# develboard.net
KiCad netlist of a schematic drawn in Altium Designer
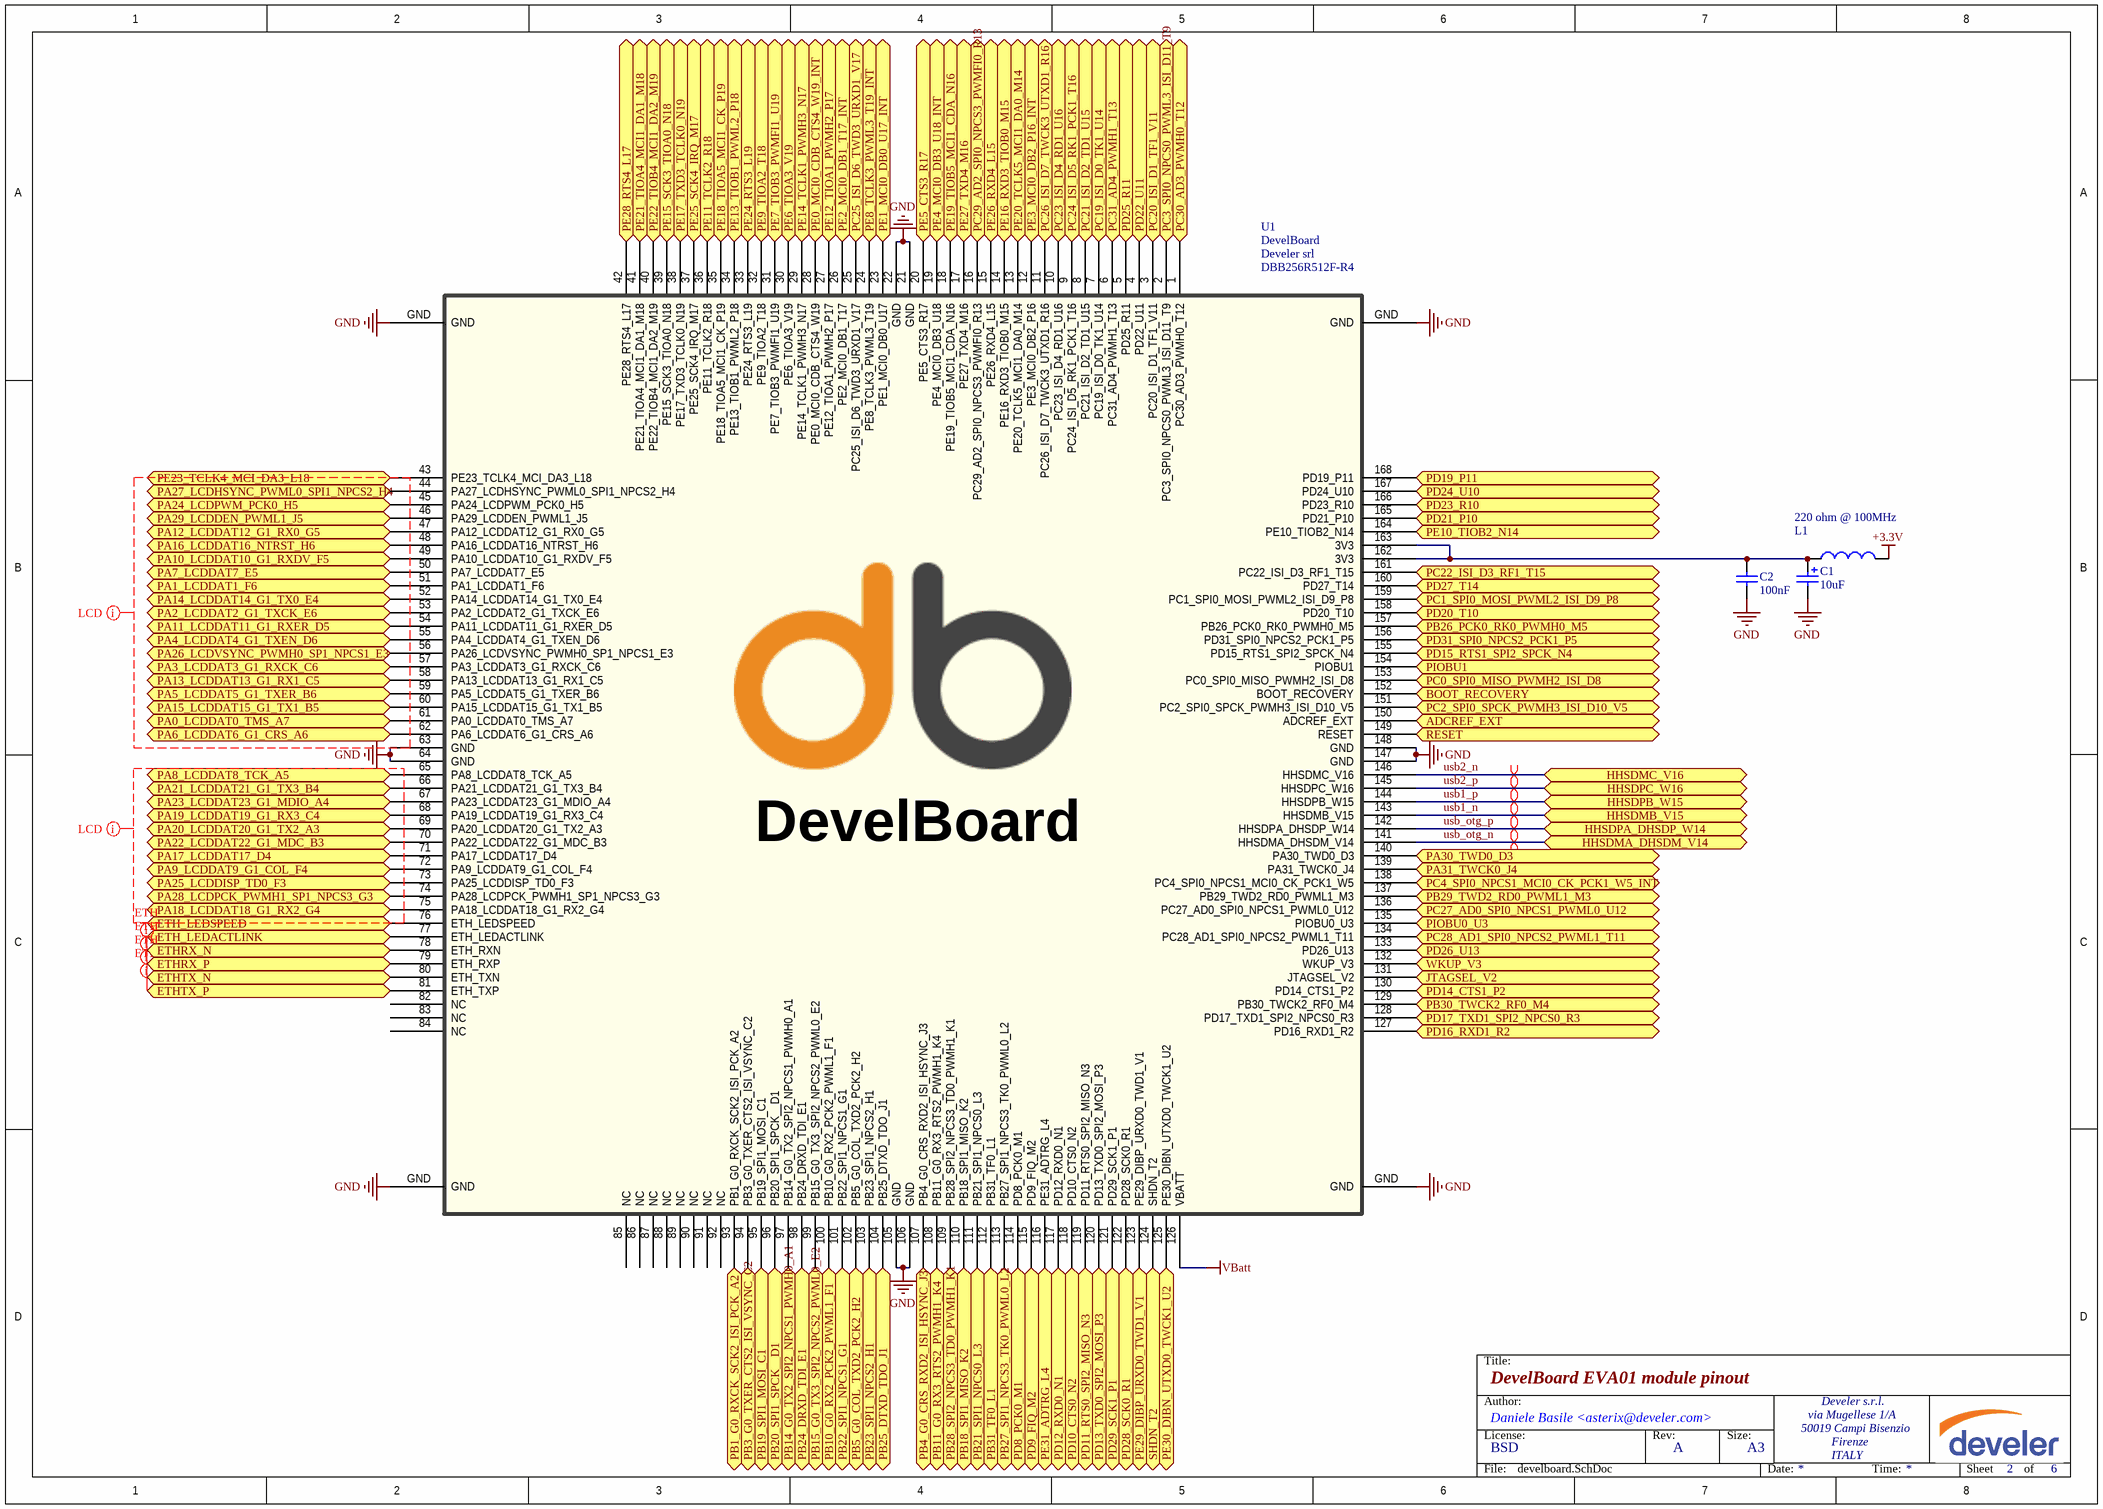
[diagram p0: develboard.SchDoc]

(export (version "E")
  (design (tool "Eeschema 10.0.6"))
  (components
    (comp (ref "C1")
      (value "10uF")
      (footprint "1206_[3216]")
      (description "Ceramic X5R 25V")
      (fields (field (name "PUBLISHER") "Altium Limited"))
      (libsource (lib "DEVELER_Library") (part "Cap Pol1"))
    )
    (comp (ref "C2")
      (value "100nF")
      (footprint "0603_[1608]")
      (description "Ceramic X7R 50V")
      (fields (field (name "PUBLISHER") "Altium Limited"))
      (libsource (lib "Miscellaneous Devices") (part "Cap"))
    )
    (comp (ref "L1")
      (value "220 ohm @ 100MHz")
      (footprint "0805_[2012]")
      (description "WE 742792022")
      (libsource (lib "DEVELER_Library") (part "Inductor"))
    )
    (comp (ref "U1")
      (value "DevelBoard")
      (footprint "develboard_footprint")
      (description "Faster Little Linux Module")
      (fields (field (name "COMPANY") "Develer srl") (field (name "ORDER CODE") "DBB256R512F-R4"))
      (libsource (lib "develboard_symbol") (part "develboard_pinout"))
    )
  )
  (nets
    (net (code "1") (name "+3.3V") (class "Default")
      (node (ref "L1") (pin "1") (pinfunction "1_1") (pintype "passive"))
    )
    (net (code "2") (name "/ADCREF_EXT") (class "Default")
      (node (ref "U1") (pin "150") (pinfunction "ADCREF_EXT_150") (pintype "passive"))
    )
    (net (code "3") (name "/BOOT_RECOVERY") (class "Default")
      (node (ref "U1") (pin "152") (pinfunction "BOOT_RECOVERY_152") (pintype "passive"))
    )
    (net (code "4") (name "/ETHRX_N") (class "Default")
      (node (ref "U1") (pin "78") (pinfunction "ETH_RXN_78") (pintype "passive"))
    )
    (net (code "5") (name "/ETHRX_P") (class "Default")
      (node (ref "U1") (pin "79") (pinfunction "ETH_RXP_79") (pintype "passive"))
    )
    (net (code "6") (name "/ETHTX_N") (class "Default")
      (node (ref "U1") (pin "80") (pinfunction "ETH_TXN_80") (pintype "passive"))
    )
    (net (code "7") (name "/ETHTX_P") (class "Default")
      (node (ref "U1") (pin "81") (pinfunction "ETH_TXP_81") (pintype "passive"))
    )
    (net (code "8") (name "/ETH_LEDACTLINK") (class "Default")
      (node (ref "U1") (pin "77") (pinfunction "ETH_LEDACTLINK_77") (pintype "passive"))
    )
    (net (code "9") (name "/ETH_LEDSPEED") (class "Default")
      (node (ref "U1") (pin "76") (pinfunction "ETH_LEDSPEED_76") (pintype "passive"))
    )
    (net (code "10") (name "/JTAGSEL_V2") (class "Default")
      (node (ref "U1") (pin "131") (pinfunction "JTAGSEL_V2_131") (pintype "passive"))
    )
    (net (code "11") (name "/PA0_LCDDAT0_TMS_A7") (class "Default")
      (node (ref "U1") (pin "61") (pinfunction "PA0_LCDDAT0_TMS_A7_61") (pintype "passive"))
    )
    (net (code "12") (name "/PA1_LCDDAT1_F6") (class "Default")
      (node (ref "U1") (pin "51") (pinfunction "PA1_LCDDAT1_F6_51") (pintype "passive"))
    )
    (net (code "13") (name "/PA2_LCDDAT2_G1_TXCK_E6") (class "Default")
      (node (ref "U1") (pin "53") (pinfunction "PA2_LCDDAT2_G1_TXCK_E6_53") (pintype "passive"))
    )
    (net (code "14") (name "/PA3_LCDDAT3_G1_RXCK_C6") (class "Default")
      (node (ref "U1") (pin "57") (pinfunction "PA3_LCDDAT3_G1_RXCK_C6_57") (pintype "passive"))
    )
    (net (code "15") (name "/PA4_LCDDAT4_G1_TXEN_D6") (class "Default")
      (node (ref "U1") (pin "55") (pinfunction "PA4_LCDDAT4_G1_TXEN_D6_55") (pintype "passive"))
    )
    (net (code "16") (name "/PA5_LCDDAT5_G1_TXER_B6") (class "Default")
      (node (ref "U1") (pin "59") (pinfunction "PA5_LCDDAT5_G1_TXER_B6_59") (pintype "passive"))
    )
    (net (code "17") (name "/PA6_LCDDAT6_G1_CRS_A6") (class "Default")
      (node (ref "U1") (pin "62") (pinfunction "PA6_LCDDAT6_G1_CRS_A6_62") (pintype "passive"))
    )
    (net (code "18") (name "/PA7_LCDDAT7_E5") (class "Default")
      (node (ref "U1") (pin "50") (pinfunction "PA7_LCDDAT7_E5_50") (pintype "passive"))
    )
    (net (code "19") (name "/PA8_LCDDAT8_TCK_A5") (class "Default")
      (node (ref "U1") (pin "65") (pinfunction "PA8_LCDDAT8_TCK_A5_65") (pintype "passive"))
    )
    (net (code "20") (name "/PA9_LCDDAT9_G1_COL_F4") (class "Default")
      (node (ref "U1") (pin "72") (pinfunction "PA9_LCDDAT9_G1_COL_F4_72") (pintype "passive"))
    )
    (net (code "21") (name "/PA10_LCDDAT10_G1_RXDV_F5") (class "Default")
      (node (ref "U1") (pin "49") (pinfunction "PA10_LCDDAT10_G1_RXDV_F5_49") (pintype "passive"))
    )
    (net (code "22") (name "/PA11_LCDDAT11_G1_RXER_D5") (class "Default")
      (node (ref "U1") (pin "54") (pinfunction "PA11_LCDDAT11_G1_RXER_D5_54") (pintype "passive"))
    )
    (net (code "23") (name "/PA12_LCDDAT12_G1_RX0_G5") (class "Default")
      (node (ref "U1") (pin "47") (pinfunction "PA12_LCDDAT12_G1_RX0_G5_47") (pintype "passive"))
    )
    (net (code "24") (name "/PA13_LCDDAT13_G1_RX1_C5") (class "Default")
      (node (ref "U1") (pin "58") (pinfunction "PA13_LCDDAT13_G1_RX1_C5_58") (pintype "passive"))
    )
    (net (code "25") (name "/PA14_LCDDAT14_G1_TX0_E4") (class "Default")
      (node (ref "U1") (pin "52") (pinfunction "PA14_LCDDAT14_G1_TX0_E4_52") (pintype "passive"))
    )
    (net (code "26") (name "/PA15_LCDDAT15_G1_TX1_B5") (class "Default")
      (node (ref "U1") (pin "60") (pinfunction "PA15_LCDDAT15_G1_TX1_B5_60") (pintype "passive"))
    )
    (net (code "27") (name "/PA16_LCDDAT16_NTRST_H6") (class "Default")
      (node (ref "U1") (pin "48") (pinfunction "PA16_LCDDAT16_NTRST_H6_48") (pintype "passive"))
    )
    (net (code "28") (name "/PA17_LCDDAT17_D4") (class "Default")
      (node (ref "U1") (pin "71") (pinfunction "PA17_LCDDAT17_D4_71") (pintype "passive"))
    )
    (net (code "29") (name "/PA18_LCDDAT18_G1_RX2_G4") (class "Default")
      (node (ref "U1") (pin "75") (pinfunction "PA18_LCDDAT18_G1_RX2_G4_75") (pintype "passive"))
    )
    (net (code "30") (name "/PA19_LCDDAT19_G1_RX3_C4") (class "Default")
      (node (ref "U1") (pin "68") (pinfunction "PA19_LCDDAT19_G1_RX3_C4_68") (pintype "passive"))
    )
    (net (code "31") (name "/PA20_LCDDAT20_G1_TX2_A3") (class "Default")
      (node (ref "U1") (pin "69") (pinfunction "PA20_LCDDAT20_G1_TX2_A3_69") (pintype "passive"))
    )
    (net (code "32") (name "/PA21_LCDDAT21_G1_TX3_B4") (class "Default")
      (node (ref "U1") (pin "66") (pinfunction "PA21_LCDDAT21_G1_TX3_B4_66") (pintype "passive"))
    )
    (net (code "33") (name "/PA22_LCDDAT22_G1_MDC_B3") (class "Default")
      (node (ref "U1") (pin "70") (pinfunction "PA22_LCDDAT22_G1_MDC_B3_70") (pintype "passive"))
    )
    (net (code "34") (name "/PA23_LCDDAT23_G1_MDIO_A4") (class "Default")
      (node (ref "U1") (pin "67") (pinfunction "PA23_LCDDAT23_G1_MDIO_A4_67") (pintype "passive"))
    )
    (net (code "35") (name "/PA24_LCDPWM_PCK0_H5") (class "Default")
      (node (ref "U1") (pin "45") (pinfunction "PA24_LCDPWM_PCK0_H5_45") (pintype "passive"))
    )
    (net (code "36") (name "/PA25_LCDDISP_TD0_F3") (class "Default")
      (node (ref "U1") (pin "73") (pinfunction "PA25_LCDDISP_TD0_F3_73") (pintype "passive"))
    )
    (net (code "37") (name "/PA26_LCDVSYNC_PWMH0_SP1_NPCS1_E3") (class "Default")
      (node (ref "U1") (pin "56") (pinfunction "PA26_LCDVSYNC_PWMH0_SP1_NPCS1_E3_56") (pintype "passive"))
    )
    (net (code "38") (name "/PA27_LCDHSYNC_PWML0_SPI1_NPCS2_H4") (class "Default")
      (node (ref "U1") (pin "44") (pinfunction "PA27_LCDHSYNC_PWML0_SPI1_NPCS2_H4_44") (pintype "passive"))
    )
    (net (code "39") (name "/PA28_LCDPCK_PWMH1_SP1_NPCS3_G3") (class "Default")
      (node (ref "U1") (pin "74") (pinfunction "PA28_LCDPCK_PWMH1_SP1_NPCS3_G3_74") (pintype "passive"))
    )
    (net (code "40") (name "/PA29_LCDDEN_PWML1_J5") (class "Default")
      (node (ref "U1") (pin "46") (pinfunction "PA29_LCDDEN_PWML1_J5_46") (pintype "passive"))
    )
    (net (code "41") (name "/PA30_TWD0_D3") (class "Default")
      (node (ref "U1") (pin "140") (pinfunction "PA30_TWD0_D3_140") (pintype "passive"))
    )
    (net (code "42") (name "/PA31_TWCK0_J4") (class "Default")
      (node (ref "U1") (pin "139") (pinfunction "PA31_TWCK0_J4_139") (pintype "passive"))
    )
    (net (code "43") (name "/PB1_G0_RXCK_SCK2_ISI_PCK_A2") (class "Default")
      (node (ref "U1") (pin "93") (pinfunction "PB1_G0_RXCK_SCK2_ISI_PCK_A2_93") (pintype "passive"))
    )
    (net (code "44") (name "/PB3_G0_TXER_CTS2_ISI_VSYNC_C2") (class "Default")
      (node (ref "U1") (pin "94") (pinfunction "PB3_G0_TXER_CTS2_ISI_VSYNC_C2_94") (pintype "passive"))
    )
    (net (code "45") (name "/PB4_G0_CRS_RXD2_ISI_HSYNC_J3") (class "Default")
      (node (ref "U1") (pin "107") (pinfunction "PB4_G0_CRS_RXD2_ISI_HSYNC_J3_107") (pintype "passive"))
    )
    (net (code "46") (name "/PB5_G0_COL_TXD2_PCK2_H2") (class "Default")
      (node (ref "U1") (pin "102") (pinfunction "PB5_G0_COL_TXD2_PCK2_H2_102") (pintype "passive"))
    )
    (net (code "47") (name "/PB10_G0_RX2_PCK2_PWML1_F1") (class "Default")
      (node (ref "U1") (pin "100") (pinfunction "PB10_G0_RX2_PCK2_PWML1_F1_100") (pintype "passive"))
    )
    (net (code "48") (name "/PB11_G0_RX3_RTS2_PWMH1_K4") (class "Default")
      (node (ref "U1") (pin "108") (pinfunction "PB11_G0_RX3_RTS2_PWMH1_K4_108") (pintype "passive"))
    )
    (net (code "49") (name "/PB14_G0_TX2_SPI2_NPCS1_PWMH0_A1") (class "Default")
      (node (ref "U1") (pin "97") (pinfunction "PB14_G0_TX2_SPI2_NPCS1_PWMH0_A1_97") (pintype "passive"))
    )
    (net (code "50") (name "/PB15_G0_TX3_SPI2_NPCS2_PWML0_E2") (class "Default")
      (node (ref "U1") (pin "99") (pinfunction "PB15_G0_TX3_SPI2_NPCS2_PWML0_E2_99") (pintype "passive"))
    )
    (net (code "51") (name "/PB18_SPI1_MISO_K2") (class "Default")
      (node (ref "U1") (pin "110") (pinfunction "PB18_SPI1_MISO_K2_110") (pintype "passive"))
    )
    (net (code "52") (name "/PB19_SPI1_MOSI_C1") (class "Default")
      (node (ref "U1") (pin "95") (pinfunction "PB19_SPI1_MOSI_C1_95") (pintype "passive"))
    )
    (net (code "53") (name "/PB20_SPI1_SPCK__D1") (class "Default")
      (node (ref "U1") (pin "96") (pinfunction "PB20_SPI1_SPCK__D1_96") (pintype "passive"))
    )
    (net (code "54") (name "/PB21_SPI1_NPCS0_L3") (class "Default")
      (node (ref "U1") (pin "111") (pinfunction "PB21_SPI1_NPCS0_L3_111") (pintype "passive"))
    )
    (net (code "55") (name "/PB22_SPI1_NPCS1_G1") (class "Default")
      (node (ref "U1") (pin "101") (pinfunction "PB22_SPI1_NPCS1_G1_101") (pintype "passive"))
    )
    (net (code "56") (name "/PB23_SPI1_NPCS2_H1") (class "Default")
      (node (ref "U1") (pin "103") (pinfunction "PB23_SPI1_NPCS2_H1_103") (pintype "passive"))
    )
    (net (code "57") (name "/PB24_DRXD_TDI_E1") (class "Default")
      (node (ref "U1") (pin "98") (pinfunction "PB24_DRXD_TDI_E1_98") (pintype "passive"))
    )
    (net (code "58") (name "/PB25_DTXD_TDO_J1") (class "Default")
      (node (ref "U1") (pin "104") (pinfunction "PB25_DTXD_TDO_J1_104") (pintype "passive"))
    )
    (net (code "59") (name "/PB26_PCK0_RK0_PWMH0_M5") (class "Default")
      (node (ref "U1") (pin "157") (pinfunction "PB26_PCK0_RK0_PWMH0_M5_157") (pintype "passive"))
    )
    (net (code "60") (name "/PB27_SPI1_NPCS3_TK0_PWML0_L2") (class "Default")
      (node (ref "U1") (pin "113") (pinfunction "PB27_SPI1_NPCS3_TK0_PWML0_L2_113") (pintype "passive"))
    )
    (net (code "61") (name "/PB28_SPI2_NPCS3_TD0_PWMH1_K1") (class "Default")
      (node (ref "U1") (pin "109") (pinfunction "PB28_SPI2_NPCS3_TD0_PWMH1_K1_109") (pintype "passive"))
    )
    (net (code "62") (name "/PB29_TWD2_RD0_PWML1_M3") (class "Default")
      (node (ref "U1") (pin "137") (pinfunction "PB29_TWD2_RD0_PWML1_M3_137") (pintype "passive"))
    )
    (net (code "63") (name "/PB30_TWCK2_RF0_M4") (class "Default")
      (node (ref "U1") (pin "129") (pinfunction "PB30_TWCK2_RF0_M4_129") (pintype "passive"))
    )
    (net (code "64") (name "/PB31_TF0_L1") (class "Default")
      (node (ref "U1") (pin "112") (pinfunction "PB31_TF0_L1_112") (pintype "passive"))
    )
    (net (code "65") (name "/PC0_SPI0_MISO_PWMH2_ISI_D8") (class "Default")
      (node (ref "U1") (pin "153") (pinfunction "PC0_SPI0_MISO_PWMH2_ISI_D8_153") (pintype "passive"))
    )
    (net (code "66") (name "/PC1_SPI0_MOSI_PWML2_ISI_D9_P8") (class "Default")
      (node (ref "U1") (pin "159") (pinfunction "PC1_SPI0_MOSI_PWML2_ISI_D9_P8_159") (pintype "passive"))
    )
    (net (code "67") (name "/PC2_SPI0_SPCK_PWMH3_ISI_D10_V5") (class "Default")
      (node (ref "U1") (pin "151") (pinfunction "PC2_SPI0_SPCK_PWMH3_ISI_D10_V5_151") (pintype "passive"))
    )
    (net (code "68") (name "/PC3_SPI0_NPCS0_PWML3_ISI_D11_T9") (class "Default")
      (node (ref "U1") (pin "2") (pinfunction "PC3_SPI0_NPCS0_PWML3_ISI_D11_T9_2") (pintype "passive"))
    )
    (net (code "69") (name "/PC4_SPI0_NPCS1_MCI0_CK_PCK1_W5_INT") (class "Default")
      (node (ref "U1") (pin "138") (pinfunction "PC4_SPI0_NPCS1_MCI0_CK_PCK1_W5_138") (pintype "passive"))
    )
    (net (code "70") (name "/PC19_ISI_D0_TK1_U14") (class "Default")
      (node (ref "U1") (pin "7") (pinfunction "PC19_ISI_D0_TK1_U14_7") (pintype "passive"))
    )
    (net (code "71") (name "/PC20_ISI_D1_TF1_V11") (class "Default")
      (node (ref "U1") (pin "3") (pinfunction "PC20_ISI_D1_TF1_V11_3") (pintype "passive"))
    )
    (net (code "72") (name "/PC21_ISI_D2_TD1_U15") (class "Default")
      (node (ref "U1") (pin "8") (pinfunction "PC21_ISI_D2_TD1_U15_8") (pintype "passive"))
    )
    (net (code "73") (name "/PC22_ISI_D3_RF1_T15") (class "Default")
      (node (ref "U1") (pin "161") (pinfunction "PC22_ISI_D3_RF1_T15_161") (pintype "passive"))
    )
    (net (code "74") (name "/PC23_ISI_D4_RD1_U16") (class "Default")
      (node (ref "U1") (pin "10") (pinfunction "PC23_ISI_D4_RD1_U16_10") (pintype "passive"))
    )
    (net (code "75") (name "/PC24_ISI_D5_RK1_PCK1_T16") (class "Default")
      (node (ref "U1") (pin "9") (pinfunction "PC24_ISI_D5_RK1_PCK1_T16_9") (pintype "passive"))
    )
    (net (code "76") (name "/PC25_ISI_D6_TWD3_URXD1_V17") (class "Default")
      (node (ref "U1") (pin "25") (pinfunction "PC25_ISI_D6_TWD3_URXD1_V17_25") (pintype "passive"))
    )
    (net (code "77") (name "/PC26_ISI_D7_TWCK3_UTXD1_R16") (class "Default")
      (node (ref "U1") (pin "11") (pinfunction "PC26_ISI_D7_TWCK3_UTXD1_R16_11") (pintype "passive"))
    )
    (net (code "78") (name "/PC27_AD0_SPI0_NPCS1_PWML0_U12") (class "Default")
      (node (ref "U1") (pin "136") (pinfunction "PC27_AD0_SPI0_NPCS1_PWML0_U12_136") (pintype "passive"))
    )
    (net (code "79") (name "/PC28_AD1_SPI0_NPCS2_PWML1_T11") (class "Default")
      (node (ref "U1") (pin "134") (pinfunction "PC28_AD1_SPI0_NPCS2_PWML1_T11_134") (pintype "passive"))
    )
    (net (code "80") (name "/PC29_AD2_SPI0_NPCS3_PWMFI0_R13") (class "Default")
      (node (ref "U1") (pin "16") (pinfunction "PC29_AD2_SPI0_NPCS3_PWMFI0_R13_16") (pintype "passive"))
    )
    (net (code "81") (name "/PC30_AD3_PWMH0_T12") (class "Default")
      (node (ref "U1") (pin "1") (pinfunction "PC30_AD3_PWMH0_T12_1") (pintype "passive"))
    )
    (net (code "82") (name "/PC31_AD4_PWMH1_T13") (class "Default")
      (node (ref "U1") (pin "6") (pinfunction "PC31_AD4_PWMH1_T13_6") (pintype "passive"))
    )
    (net (code "83") (name "/PD8_PCK0_M1") (class "Default")
      (node (ref "U1") (pin "114") (pinfunction "PD8_PCK0_M1_114") (pintype "passive"))
    )
    (net (code "84") (name "/PD9_FIQ_M2") (class "Default")
      (node (ref "U1") (pin "115") (pinfunction "PD9_FIQ_M2_115") (pintype "passive"))
    )
    (net (code "85") (name "/PD10_CTS0_N2") (class "Default")
      (node (ref "U1") (pin "118") (pinfunction "PD10_CTS0_N2_118") (pintype "passive"))
    )
    (net (code "86") (name "/PD11_RTS0_SPI2_MISO_N3") (class "Default")
      (node (ref "U1") (pin "119") (pinfunction "PD11_RTS0_SPI2_MISO_N3_119") (pintype "passive"))
    )
    (net (code "87") (name "/PD12_RXD0_N1") (class "Default")
      (node (ref "U1") (pin "117") (pinfunction "PD12_RXD0_N1_117") (pintype "passive"))
    )
    (net (code "88") (name "/PD13_TXD0_SPI2_MOSI_P3") (class "Default")
      (node (ref "U1") (pin "120") (pinfunction "PD13_TXD0_SPI2_MOSI_P3_120") (pintype "passive"))
    )
    (net (code "89") (name "/PD14_CTS1_P2") (class "Default")
      (node (ref "U1") (pin "130") (pinfunction "PD14_CTS1_P2_130") (pintype "passive"))
    )
    (net (code "90") (name "/PD15_RTS1_SPI2_SPCK_N4") (class "Default")
      (node (ref "U1") (pin "155") (pinfunction "PD15_RTS1_SPI2_SPCK_N4_155") (pintype "passive"))
    )
    (net (code "91") (name "/PD16_RXD1_R2") (class "Default")
      (node (ref "U1") (pin "127") (pinfunction "PD16_RXD1_R2_127") (pintype "passive"))
    )
    (net (code "92") (name "/PD17_TXD1_SPI2_NPCS0_R3") (class "Default")
      (node (ref "U1") (pin "128") (pinfunction "PD17_TXD1_SPI2_NPCS0_R3_128") (pintype "passive"))
    )
    (net (code "93") (name "/PD19_P11") (class "Default")
      (node (ref "U1") (pin "168") (pinfunction "PD19_P11_168") (pintype "passive"))
    )
    (net (code "94") (name "/PD20_T10") (class "Default")
      (node (ref "U1") (pin "158") (pinfunction "PD20_T10_158") (pintype "passive"))
    )
    (net (code "95") (name "/PD21_P10") (class "Default")
      (node (ref "U1") (pin "165") (pinfunction "PD21_P10_165") (pintype "passive"))
    )
    (net (code "96") (name "/PD22_U11") (class "Default")
      (node (ref "U1") (pin "4") (pinfunction "PD22_U11_4") (pintype "passive"))
    )
    (net (code "97") (name "/PD23_R10") (class "Default")
      (node (ref "U1") (pin "166") (pinfunction "PD23_R10_166") (pintype "passive"))
    )
    (net (code "98") (name "/PD24_U10") (class "Default")
      (node (ref "U1") (pin "167") (pinfunction "PD24_U10_167") (pintype "passive"))
    )
    (net (code "99") (name "/PD25_R11") (class "Default")
      (node (ref "U1") (pin "5") (pinfunction "PD25_R11_5") (pintype "passive"))
    )
    (net (code "100") (name "/PD26_U13") (class "Default")
      (node (ref "U1") (pin "133") (pinfunction "PD26_U13_133") (pintype "passive"))
    )
    (net (code "101") (name "/PD27_T14") (class "Default")
      (node (ref "U1") (pin "160") (pinfunction "PD27_T14_160") (pintype "passive"))
    )
    (net (code "102") (name "/PD28_SCK0_R1") (class "Default")
      (node (ref "U1") (pin "122") (pinfunction "PD28_SCK0_R1_122") (pintype "passive"))
    )
    (net (code "103") (name "/PD29_SCK1_P1") (class "Default")
      (node (ref "U1") (pin "121") (pinfunction "PD29_SCK1_P1_121") (pintype "passive"))
    )
    (net (code "104") (name "/PD31_SPI0_NPCS2_PCK1_P5") (class "Default")
      (node (ref "U1") (pin "156") (pinfunction "PD31_SPI0_NPCS2_PCK1_P5_156") (pintype "passive"))
    )
    (net (code "105") (name "/PE0_MCI0_CDB_CTS4_W19_INT") (class "Default")
      (node (ref "U1") (pin "28") (pinfunction "PE0_MCI0_CDB_CTS4_W19_28") (pintype "passive"))
    )
    (net (code "106") (name "/PE1_MCI0_DB0_U17_INT") (class "Default")
      (node (ref "U1") (pin "23") (pinfunction "PE1_MCI0_DB0_U17_23") (pintype "passive"))
    )
    (net (code "107") (name "/PE2_MCI0_DB1_T17_INT") (class "Default")
      (node (ref "U1") (pin "26") (pinfunction "PE2_MCI0_DB1_T17_26") (pintype "passive"))
    )
    (net (code "108") (name "/PE3_MCI0_DB2_P16_INT") (class "Default")
      (node (ref "U1") (pin "12") (pinfunction "PE3_MCI0_DB2_P16_12") (pintype "passive"))
    )
    (net (code "109") (name "/PE4_MCI0_DB3_U18_INT") (class "Default")
      (node (ref "U1") (pin "19") (pinfunction "PE4_MCI0_DB3_U18_19") (pintype "passive"))
    )
    (net (code "110") (name "/PE5_CTS3_R17") (class "Default")
      (node (ref "U1") (pin "20") (pinfunction "PE5_CTS3_R17_20") (pintype "passive"))
    )
    (net (code "111") (name "/PE6_TIOA3_V19") (class "Default")
      (node (ref "U1") (pin "30") (pinfunction "PE6_TIOA3_V19_30") (pintype "passive"))
    )
    (net (code "112") (name "/PE7_TIOB3_PWMFI1_U19") (class "Default")
      (node (ref "U1") (pin "31") (pinfunction "PE7_TIOB3_PWMFI1_U19_31") (pintype "passive"))
    )
    (net (code "113") (name "/PE8_TCLK3_PWML3_T19_INT") (class "Default")
      (node (ref "U1") (pin "24") (pinfunction "PE8_TCLK3_PWML3_T19_24") (pintype "passive"))
    )
    (net (code "114") (name "/PE9_TIOA2_T18") (class "Default")
      (node (ref "U1") (pin "32") (pinfunction "PE9_TIOA2_T18_32") (pintype "passive"))
    )
    (net (code "115") (name "/PE10_TIOB2_N14") (class "Default")
      (node (ref "U1") (pin "164") (pinfunction "PE10_TIOB2_N14_164") (pintype "passive"))
    )
    (net (code "116") (name "/PE11_TCLK2_R18") (class "Default")
      (node (ref "U1") (pin "36") (pinfunction "PE11_TCLK2_R18_36") (pintype "passive"))
    )
    (net (code "117") (name "/PE12_TIOA1_PWMH2_P17") (class "Default")
      (node (ref "U1") (pin "27") (pinfunction "PE12_TIOA1_PWMH2_P17_27") (pintype "passive"))
    )
    (net (code "118") (name "/PE13_TIOB1_PWML2_P18") (class "Default")
      (node (ref "U1") (pin "34") (pinfunction "PE13_TIOB1_PWML2_P18_34") (pintype "passive"))
    )
    (net (code "119") (name "/PE14_TCLK1_PWMH3_N17") (class "Default")
      (node (ref "U1") (pin "29") (pinfunction "PE14_TCLK1_PWMH3_N17_29") (pintype "passive"))
    )
    (net (code "120") (name "/PE15_SCK3_TIOA0_N18") (class "Default")
      (node (ref "U1") (pin "39") (pinfunction "PE15_SCK3_TIOA0_N18_39") (pintype "passive"))
    )
    (net (code "121") (name "/PE16_RXD3_TIOB0_M15") (class "Default")
      (node (ref "U1") (pin "14") (pinfunction "PE16_RXD3_TIOB0_M15_14") (pintype "passive"))
    )
    (net (code "122") (name "/PE17_TXD3_TCLK0_N19") (class "Default")
      (node (ref "U1") (pin "38") (pinfunction "PE17_TXD3_TCLK0_N19_38") (pintype "passive"))
    )
    (net (code "123") (name "/PE18_TIOA5_MCI1_CK_P19") (class "Default")
      (node (ref "U1") (pin "35") (pinfunction "PE18_TIOA5_MCI1_CK_P19_35") (pintype "passive"))
    )
    (net (code "124") (name "/PE19_TIOB5_MCI1_CDA_N16") (class "Default")
      (node (ref "U1") (pin "18") (pinfunction "PE19_TIOB5_MCI1_CDA_N16_18") (pintype "passive"))
    )
    (net (code "125") (name "/PE20_TCLK5_MCI1_DA0_M14") (class "Default")
      (node (ref "U1") (pin "13") (pinfunction "PE20_TCLK5_MCI1_DA0_M14_13") (pintype "passive"))
    )
    (net (code "126") (name "/PE21_TIOA4_MCI1_DA1_M18") (class "Default")
      (node (ref "U1") (pin "41") (pinfunction "PE21_TIOA4_MCI1_DA1_M18_41") (pintype "passive"))
    )
    (net (code "127") (name "/PE22_TIOB4_MCI1_DA2_M19") (class "Default")
      (node (ref "U1") (pin "40") (pinfunction "PE22_TIOB4_MCI1_DA2_M19_40") (pintype "passive"))
    )
    (net (code "128") (name "/PE23_TCLK4_MCI_DA3_L18") (class "Default")
      (node (ref "U1") (pin "43") (pinfunction "PE23_TCLK4_MCI_DA3_L18_43") (pintype "passive"))
    )
    (net (code "129") (name "/PE24_RTS3_L19") (class "Default")
      (node (ref "U1") (pin "33") (pinfunction "PE24_RTS3_L19_33") (pintype "passive"))
    )
    (net (code "130") (name "/PE25_SCK4_IRQ_M17") (class "Default")
      (node (ref "U1") (pin "37") (pinfunction "PE25_SCK4_IRQ_M17_37") (pintype "passive"))
    )
    (net (code "131") (name "/PE26_RXD4_L15") (class "Default")
      (node (ref "U1") (pin "15") (pinfunction "PE26_RXD4_L15_15") (pintype "passive"))
    )
    (net (code "132") (name "/PE27_TXD4_M16") (class "Default")
      (node (ref "U1") (pin "17") (pinfunction "PE27_TXD4_M16_17") (pintype "passive"))
    )
    (net (code "133") (name "/PE28_RTS4_L17") (class "Default")
      (node (ref "U1") (pin "42") (pinfunction "PE28_RTS4_L17_42") (pintype "passive"))
    )
    (net (code "134") (name "/PE29_DIBP_URXD0_TWD1_V1") (class "Default")
      (node (ref "U1") (pin "123") (pinfunction "PE29_DIBP_URXD0_TWD1_V1_123") (pintype "passive"))
    )
    (net (code "135") (name "/PE30_DIBN_UTXD0_TWCK1_U2") (class "Default")
      (node (ref "U1") (pin "125") (pinfunction "PE30_DIBN_UTXD0_TWCK1_U2_125") (pintype "passive"))
    )
    (net (code "136") (name "/PE31_ADTRG_L4") (class "Default")
      (node (ref "U1") (pin "116") (pinfunction "PE31_ADTRG_L4_116") (pintype "passive"))
    )
    (net (code "137") (name "/PIOBU0_U3") (class "Default")
      (node (ref "U1") (pin "135") (pinfunction "PIOBU0_U3_135") (pintype "passive"))
    )
    (net (code "138") (name "/PIOBU1") (class "Default")
      (node (ref "U1") (pin "154") (pinfunction "PIOBU1_154") (pintype "passive"))
    )
    (net (code "139") (name "/RESET") (class "Default")
      (node (ref "U1") (pin "149") (pinfunction "RESET_149") (pintype "passive"))
    )
    (net (code "140") (name "/SHDN_T2") (class "Default")
      (node (ref "U1") (pin "124") (pinfunction "SHDN_T2_124") (pintype "passive"))
    )
    (net (code "141") (name "/WKUP_V3") (class "Default")
      (node (ref "U1") (pin "132") (pinfunction "WKUP_V3_132") (pintype "passive"))
    )
    (net (code "142") (name "/usb1_n") (class "Default")
      (node (ref "U1") (pin "143") (pinfunction "HHSDMB_V15_143") (pintype "passive"))
    )
    (net (code "143") (name "/usb1_p") (class "Default")
      (node (ref "U1") (pin "144") (pinfunction "HHSDPB_W15_144") (pintype "passive"))
    )
    (net (code "144") (name "/usb2_n") (class "Default")
      (node (ref "U1") (pin "146") (pinfunction "HHSDMC_V16_146") (pintype "passive"))
    )
    (net (code "145") (name "/usb2_p") (class "Default")
      (node (ref "U1") (pin "145") (pinfunction "HHSDPC_W16_145") (pintype "passive"))
    )
    (net (code "146") (name "/usb_otg_n") (class "Default")
      (node (ref "U1") (pin "141") (pinfunction "HHSDMA_DHSDM_V14_141") (pintype "passive"))
    )
    (net (code "147") (name "/usb_otg_p") (class "Default")
      (node (ref "U1") (pin "142") (pinfunction "HHSDPA_DHSDP_W14_142") (pintype "passive"))
    )
    (net (code "148") (name "GND") (class "Default")
      (node (ref "C1") (pin "2") (pinfunction "2_2") (pintype "passive"))
      (node (ref "C2") (pin "2") (pinfunction "2_2") (pintype "passive"))
      (node (ref "U1") (pin "105") (pinfunction "GND_105") (pintype "passive"))
      (node (ref "U1") (pin "106") (pinfunction "GND_106") (pintype "passive"))
      (node (ref "U1") (pin "147") (pinfunction "GND_147") (pintype "passive"))
      (node (ref "U1") (pin "148") (pinfunction "GND_148") (pintype "passive"))
      (node (ref "U1") (pin "21") (pinfunction "GND_21") (pintype "passive"))
      (node (ref "U1") (pin "22") (pinfunction "GND_22") (pintype "passive"))
      (node (ref "U1") (pin "63") (pinfunction "GND_63") (pintype "passive"))
      (node (ref "U1") (pin "64") (pinfunction "GND_64") (pintype "passive"))
      (node (ref "U1") (pin "GND") (pinfunction "GND_GND") (pintype "passive"))
    )
    (net (code "149") (name "Net-(C1-Pad1)") (class "Default")
      (node (ref "C1") (pin "1") (pinfunction "1_1") (pintype "passive"))
      (node (ref "C2") (pin "1") (pinfunction "1_1") (pintype "passive"))
      (node (ref "L1") (pin "2") (pinfunction "2_2") (pintype "passive"))
      (node (ref "U1") (pin "162") (pinfunction "3V3_162") (pintype "passive"))
      (node (ref "U1") (pin "163") (pinfunction "3V3_163") (pintype "passive"))
    )
    (net (code "150") (name "VBatt") (class "Default")
      (node (ref "U1") (pin "126") (pinfunction "VBATT_126") (pintype "passive"))
    )
    (net (code "151") (name "unconnected-(U1-NC-Pad82)") (class "Default")
      (node (ref "U1") (pin "82") (pinfunction "NC_82") (pintype "passive"))
    )
    (net (code "152") (name "unconnected-(U1-NC-Pad83)") (class "Default")
      (node (ref "U1") (pin "83") (pinfunction "NC_83") (pintype "passive"))
    )
    (net (code "153") (name "unconnected-(U1-NC-Pad84)") (class "Default")
      (node (ref "U1") (pin "84") (pinfunction "NC_84") (pintype "passive"))
    )
    (net (code "154") (name "unconnected-(U1-NC-Pad85)") (class "Default")
      (node (ref "U1") (pin "85") (pinfunction "NC_85") (pintype "passive"))
    )
    (net (code "155") (name "unconnected-(U1-NC-Pad86)") (class "Default")
      (node (ref "U1") (pin "86") (pinfunction "NC_86") (pintype "passive"))
    )
    (net (code "156") (name "unconnected-(U1-NC-Pad87)") (class "Default")
      (node (ref "U1") (pin "87") (pinfunction "NC_87") (pintype "passive"))
    )
    (net (code "157") (name "unconnected-(U1-NC-Pad88)") (class "Default")
      (node (ref "U1") (pin "88") (pinfunction "NC_88") (pintype "passive"))
    )
    (net (code "158") (name "unconnected-(U1-NC-Pad89)") (class "Default")
      (node (ref "U1") (pin "89") (pinfunction "NC_89") (pintype "passive"))
    )
    (net (code "159") (name "unconnected-(U1-NC-Pad90)") (class "Default")
      (node (ref "U1") (pin "90") (pinfunction "NC_90") (pintype "passive"))
    )
    (net (code "160") (name "unconnected-(U1-NC-Pad91)") (class "Default")
      (node (ref "U1") (pin "91") (pinfunction "NC_91") (pintype "passive"))
    )
    (net (code "161") (name "unconnected-(U1-NC-Pad92)") (class "Default")
      (node (ref "U1") (pin "92") (pinfunction "NC_92") (pintype "passive"))
    )
  )
)
